# Buck.net
KiCad netlist of a schematic drawn in Altium Designer
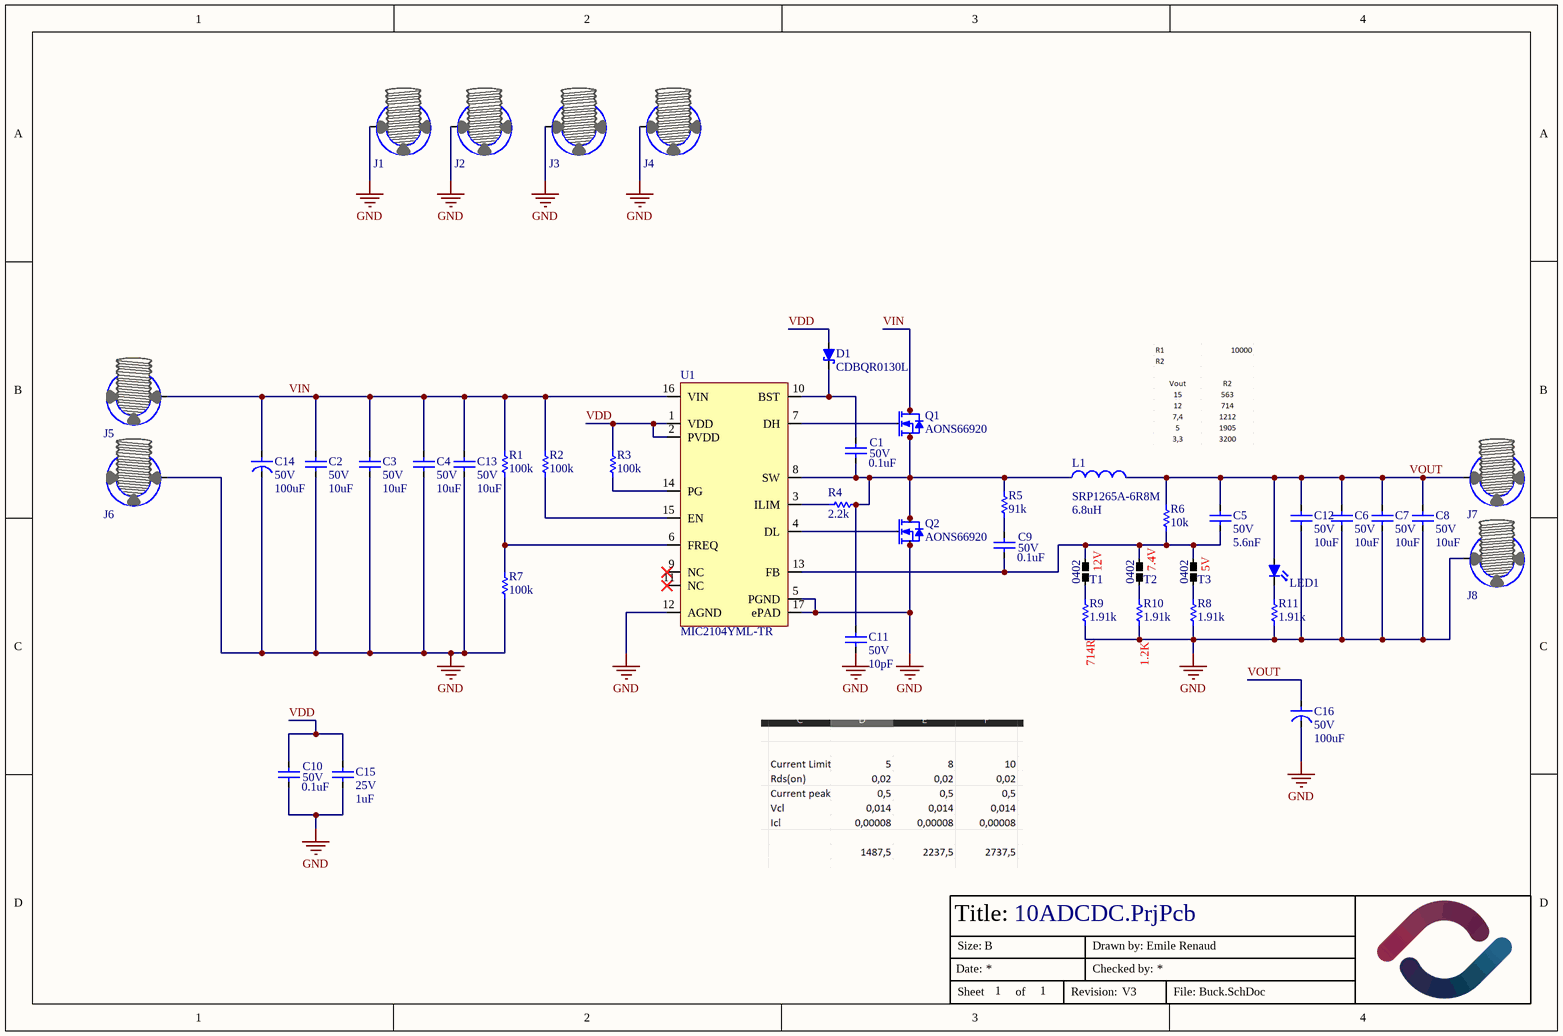
[diagram p0: Buck.SchDoc]

(export (version "E")
  (design (tool "Eeschema 10.0.6"))
  (components
    (comp (ref "C1")
      (value "0.1uF")
      (footprint "CAPACITOR-0603")
      (description "Capacitor-0603-0.1uF-50V-X7R")
      (fields (field (name "VOLT") "50V"))
      (libsource (lib "Capacitors") (part "Capacitor-0603-0.1uF-50V-X7R"))
    )
    (comp (ref "C2")
      (value "10uF")
      (footprint "CAPACITOR-1206")
      (description "Capacitor-1206-10uF-50V-X5R")
      (fields (field (name "VOLT") "50V"))
      (libsource (lib "Capacitors") (part "Capacitor-1206-10uF-50V-X5R"))
    )
    (comp (ref "C3")
      (value "10uF")
      (footprint "CAPACITOR-1206")
      (description "Capacitor-1206-10uF-50V-X5R")
      (fields (field (name "VOLT") "50V"))
      (libsource (lib "Capacitors") (part "Capacitor-1206-10uF-50V-X5R"))
    )
    (comp (ref "C4")
      (value "10uF")
      (footprint "CAPACITOR-1206")
      (description "Capacitor-1206-10uF-50V-X5R")
      (fields (field (name "VOLT") "50V"))
      (libsource (lib "Capacitors") (part "Capacitor-1206-10uF-50V-X5R"))
    )
    (comp (ref "C5")
      (value "5.6nF")
      (footprint "CAPACITOR-0603")
      (description "Capacitor-0603-5.6nF-50V-X7R")
      (fields (field (name "VOLT") "50V") (field (name "Comment") "Capacitor-0603-0.1uF-50V-X7R"))
      (libsource (lib "Capacitors") (part "Capacitor-0603-5.6nF-50V-X7R"))
    )
    (comp (ref "C6")
      (value "10uF")
      (footprint "CAPACITOR-1206")
      (description "Capacitor-1206-10uF-50V-X5R")
      (fields (field (name "VOLT") "50V"))
      (libsource (lib "Capacitors") (part "Capacitor-1206-10uF-50V-X5R"))
    )
    (comp (ref "C7")
      (value "10uF")
      (footprint "CAPACITOR-1206")
      (description "Capacitor-1206-10uF-50V-X5R")
      (fields (field (name "VOLT") "50V"))
      (libsource (lib "Capacitors") (part "Capacitor-1206-10uF-50V-X5R"))
    )
    (comp (ref "C8")
      (value "10uF")
      (footprint "CAPACITOR-1206")
      (description "Capacitor-1206-10uF-50V-X5R")
      (fields (field (name "VOLT") "50V"))
      (libsource (lib "Capacitors") (part "Capacitor-1206-10uF-50V-X5R"))
    )
    (comp (ref "C9")
      (value "0.1uF")
      (footprint "CAPACITOR-0603")
      (description "Capacitor-0603-0.1uF-50V-X7R")
      (fields (field (name "VOLT") "50V"))
      (libsource (lib "Capacitors") (part "Capacitor-0603-0.1uF-50V-X7R"))
    )
    (comp (ref "C10")
      (value "0.1uF")
      (footprint "CAPACITOR-0603")
      (description "Capacitor-0603-0.1uF-50V-X7R")
      (fields (field (name "VOLT") "50V"))
      (libsource (lib "Capacitors") (part "Capacitor-0603-0.1uF-50V-X7R"))
    )
    (comp (ref "C11")
      (value "10pF")
      (footprint "CAPACITOR-0603")
      (description "10 pF ±5% 50V Ceramic Capacitor C0G 0603 (1608 Metric)")
      (fields (field (name "VOLT") "50V") (field (name "Comment") "Capacitor-0603-10pF-50V-C0G"))
      (libsource (lib "Capacitors") (part "Capacitor-0603-10pF-50V-C0G"))
    )
    (comp (ref "C12")
      (value "10uF")
      (footprint "CAPACITOR-1206")
      (description "Capacitor-1206-10uF-50V-X5R")
      (fields (field (name "VOLT") "50V"))
      (libsource (lib "Capacitors") (part "Capacitor-1206-10uF-50V-X5R"))
    )
    (comp (ref "C13")
      (value "10uF")
      (footprint "CAPACITOR-1206")
      (description "Capacitor-1206-10uF-50V-X5R")
      (fields (field (name "VOLT") "50V"))
      (libsource (lib "Capacitors") (part "Capacitor-1206-10uF-50V-X5R"))
    )
    (comp (ref "C14")
      (value "100uF")
      (footprint "CAP_J-V_8X10P5_RUB")
      (description "CAP ALUM 100UF 20% 50V SMD")
      (fields (field (name "VOLT") "50V") (field (name "Comment") "CAP ALUM 100UF 20% 25V SMD"))
      (libsource (lib "Capacitors-Electrolytic") (part "Capacitor-100uF-50V-SMD"))
    )
    (comp (ref "C15")
      (value "1uF")
      (footprint "CAPACITOR-0603")
      (description "Capacitor-0603-1uF-25V-X5R")
      (fields (field (name "VOLT") "25V"))
      (libsource (lib "Capacitors") (part "Capacitor-0603-1uF-25V-X5R"))
    )
    (comp (ref "C16")
      (value "100uF")
      (footprint "CAP_J-V_8X10P5_RUB")
      (description "CAP ALUM 100UF 20% 50V SMD")
      (fields (field (name "VOLT") "50V") (field (name "Comment") "CAP ALUM 100UF 20% 25V SMD"))
      (libsource (lib "Capacitors-Electrolytic") (part "Capacitor-100uF-50V-SMD"))
    )
    (comp (ref "D1")
      (value "CDBQR0130L")
      (footprint "Diode-0402")
      (description "Diode SCHOTTKY  30 V 100mA Surface Mount 0402/SOD-923F")
      (libsource (lib "diodes") (part "CDBQR0130L"))
    )
    (comp (ref "J1")
      (value "hole")
      (footprint "HOLE-M2-Bolt")
      (description "Hole for M2 Bolt with 4mm pad")
      (libsource (lib "JumpersAndHoles") (part "Hole 2.3mm M2"))
    )
    (comp (ref "J2")
      (value "hole")
      (footprint "HOLE-M2-Bolt")
      (description "Hole for M2 Bolt with 4mm pad")
      (libsource (lib "JumpersAndHoles") (part "Hole 2.3mm M2"))
    )
    (comp (ref "J3")
      (value "hole")
      (footprint "HOLE-M2-Bolt")
      (description "Hole for M2 Bolt with 4mm pad")
      (libsource (lib "JumpersAndHoles") (part "Hole 2.3mm M2"))
    )
    (comp (ref "J4")
      (value "hole")
      (footprint "HOLE-M2-Bolt")
      (description "Hole for M2 Bolt with 4mm pad")
      (libsource (lib "JumpersAndHoles") (part "Hole 2.3mm M2"))
    )
    (comp (ref "J5")
      (value "hole")
      (footprint "HOLE-M2-Bolt")
      (description "Hole for M2 Bolt with 4mm pad")
      (libsource (lib "") (part "Hole 2.3mm M2_1"))
    )
    (comp (ref "J6")
      (value "hole")
      (footprint "HOLE-M2-Bolt")
      (description "Hole for M2 Bolt with 4mm pad")
      (libsource (lib "") (part "Hole 2.3mm M2_1"))
    )
    (comp (ref "J7")
      (value "hole")
      (footprint "HOLE-M2-Bolt")
      (description "Hole for M2 Bolt with 4mm pad")
      (libsource (lib "JumpersAndHoles") (part "Hole 2.3mm M2"))
    )
    (comp (ref "J8")
      (value "hole")
      (footprint "HOLE-M2-Bolt")
      (description "Hole for M2 Bolt with 4mm pad")
      (libsource (lib "JumpersAndHoles") (part "Hole 2.3mm M2"))
    )
    (comp (ref "L1")
      (value "SRP1265A-6R8M")
      (footprint "IND_SRP1265A-6R8M")
      (description "6.8 µH Shielded Drum Core, Wirewound Inductor 11.5 A 11.5mOhm Max Nonstandard")
      (fields (field (name "ALTIUM_VALUE") "6.8uH"))
      (libsource (lib "Inductors") (part "SRP1265A-6R8M"))
    )
    (comp (ref "LED1")
      (value "3147-B1931NB--20C007614U1930CT-ND")
      (footprint "LED-0603-2PIN")
      (description "LED BLUE CLEAR 0603 SMD")
      (libsource (lib "LEDs") (part "LED_BLUE"))
    )
    (comp (ref "Q1")
      (value "AONS66920")
      (footprint "DFN-8-5x6-Power")
      (description "N-Channel 100 V 17.5A (Ta), 48A (Tc) 5W (Ta), 56.5W (Tc) Surface Mount 8-DFN (5x6)")
      (libsource (lib "FET-N-Small") (part "AONS66920"))
    )
    (comp (ref "Q2")
      (value "AONS66920")
      (footprint "DFN-8-5x6-Power")
      (description "N-Channel 100 V 17.5A (Ta), 48A (Tc) 5W (Ta), 56.5W (Tc) Surface Mount 8-DFN (5x6)")
      (libsource (lib "FET-N-Small") (part "AONS66920"))
    )
    (comp (ref "R1")
      (value "100k")
      (footprint "Resistor-0603")
      (description "Resistor0603-100k")
      (fields (field (name "Comment") "SMT resistor"))
      (libsource (lib "Resistors") (part "Resistor-0603-100k"))
    )
    (comp (ref "R2")
      (value "100k")
      (footprint "Resistor-0603")
      (description "Resistor0603-100k")
      (fields (field (name "Comment") "SMT resistor"))
      (libsource (lib "Resistors") (part "Resistor-0603-100k"))
    )
    (comp (ref "R3")
      (value "100k")
      (footprint "Resistor-0603")
      (description "Resistor0603-100k")
      (fields (field (name "Comment") "SMT resistor"))
      (libsource (lib "Resistors") (part "Resistor-0603-100k"))
    )
    (comp (ref "R4")
      (value "2.2k")
      (footprint "Resistor-0603")
      (description "Resistor0603-2.2k")
      (fields (field (name "Comment") "SMT resistor"))
      (libsource (lib "Resistors") (part "Resistor-0603-2.2k"))
    )
    (comp (ref "R5")
      (value "91k")
      (footprint "Resistor-0603")
      (description "Resistor0603-91k")
      (fields (field (name "Comment") "SMT resistor"))
      (libsource (lib "Resistors") (part "Resistor-0603-91k"))
    )
    (comp (ref "R6")
      (value "10k")
      (footprint "Resistor-0603")
      (description "Resistor0603-10k")
      (fields (field (name "Comment") "SMT resistor"))
      (libsource (lib "Resistors") (part "Resistor-0603-10k"))
    )
    (comp (ref "R7")
      (value "100k")
      (footprint "Resistor-0603")
      (description "Resistor0603-100k")
      (fields (field (name "Comment") "SMT resistor"))
      (libsource (lib "Resistors") (part "Resistor-0603-100k"))
    )
    (comp (ref "R8")
      (value "1.91k")
      (footprint "Resistor-0603")
      (description "Resistor0603-1.91k")
      (fields (field (name "Comment") "SMT resistor"))
      (libsource (lib "Resistors") (part "Resistor-0603-1.91k"))
    )
    (comp (ref "R9")
      (value "1.91k")
      (footprint "Resistor-0603")
      (description "Resistor0603-1.91k")
      (fields (field (name "Comment") "SMT resistor"))
      (libsource (lib "Resistors") (part "Resistor-0603-1.91k"))
    )
    (comp (ref "R10")
      (value "1.91k")
      (footprint "Resistor-0603")
      (description "Resistor0603-1.91k")
      (fields (field (name "Comment") "SMT resistor"))
      (libsource (lib "Resistors") (part "Resistor-0603-1.91k"))
    )
    (comp (ref "R11")
      (value "1.91k")
      (footprint "Resistor-0603")
      (description "Resistor0603-1.91k")
      (fields (field (name "Comment") "SMT resistor"))
      (libsource (lib "Resistors") (part "Resistor-0603-1.91k"))
    )
    (comp (ref "T1")
      (value "NetTie_0402")
      (footprint "NetTie-0402")
      (libsource (lib "JumpersAndHoles") (part "NetTie_0402"))
    )
    (comp (ref "T2")
      (value "NetTie_0402")
      (footprint "NetTie-0402")
      (libsource (lib "JumpersAndHoles") (part "NetTie_0402"))
    )
    (comp (ref "T3")
      (value "NetTie_0402")
      (footprint "NetTie-0402")
      (libsource (lib "JumpersAndHoles") (part "NetTie_0402"))
    )
    (comp (ref "U1")
      (value "MIC2104YML-TR")
      (footprint "VQFN-16 3x3")
      (description "Buck Regulator Positive Output Step-Down DC-DC Controller IC 16-MLF® (3x3)")
      (libsource (lib "PMIC-VoltageRegulators-DCDCSwitchingRegulators") (part "MIC2104YML-TR"))
    )
  )
  (nets
    (net (code "1") (name "/VDD") (class "Default")
      (node (ref "C10") (pin "2") (pinfunction "2_2") (pintype "passive"))
      (node (ref "C15") (pin "2") (pinfunction "2_2") (pintype "passive"))
      (node (ref "D1") (pin "1") (pinfunction "A_1") (pintype "passive"))
      (node (ref "R3") (pin "2") (pinfunction "2_2") (pintype "passive"))
      (node (ref "U1") (pin "1") (pinfunction "VDD_1") (pintype "passive"))
      (node (ref "U1") (pin "2") (pinfunction "PVDD_2") (pintype "passive"))
    )
    (net (code "2") (name "/VIN") (class "Default")
      (node (ref "C13") (pin "2") (pinfunction "2_2") (pintype "passive"))
      (node (ref "C14") (pin "1") (pinfunction "1_1") (pintype "passive"))
      (node (ref "C2") (pin "2") (pinfunction "2_2") (pintype "passive"))
      (node (ref "C3") (pin "2") (pinfunction "2_2") (pintype "passive"))
      (node (ref "C4") (pin "2") (pinfunction "2_2") (pintype "passive"))
      (node (ref "J5") (pin "1") (pinfunction "1_1") (pintype "passive"))
      (node (ref "Q1") (pin "5") (pinfunction "D_5") (pintype "passive"))
      (node (ref "Q1") (pin "6") (pinfunction "D_6") (pintype "passive"))
      (node (ref "Q1") (pin "7") (pinfunction "D_7") (pintype "passive"))
      (node (ref "Q1") (pin "8") (pinfunction "D_8") (pintype "passive"))
      (node (ref "R1") (pin "2") (pinfunction "2_2") (pintype "passive"))
      (node (ref "R2") (pin "2") (pinfunction "2_2") (pintype "passive"))
      (node (ref "U1") (pin "16") (pinfunction "VIN_16") (pintype "passive"))
    )
    (net (code "3") (name "/VOUT") (class "Default")
      (node (ref "C12") (pin "2") (pinfunction "2_2") (pintype "passive"))
      (node (ref "C16") (pin "1") (pinfunction "1_1") (pintype "passive"))
      (node (ref "C5") (pin "2") (pinfunction "2_2") (pintype "passive"))
      (node (ref "C6") (pin "2") (pinfunction "2_2") (pintype "passive"))
      (node (ref "C7") (pin "2") (pinfunction "2_2") (pintype "passive"))
      (node (ref "C8") (pin "2") (pinfunction "2_2") (pintype "passive"))
      (node (ref "J7") (pin "1") (pinfunction "1_1") (pintype "passive"))
      (node (ref "L1") (pin "2") (pinfunction "2_2") (pintype "passive"))
      (node (ref "LED1") (pin "2") (pinfunction "R_2") (pintype "passive"))
      (node (ref "R6") (pin "2") (pinfunction "2_2") (pintype "passive"))
    )
    (net (code "4") (name "GND") (class "Default")
      (node (ref "C10") (pin "1") (pinfunction "1_1") (pintype "passive"))
      (node (ref "C11") (pin "1") (pinfunction "1_1") (pintype "passive"))
      (node (ref "C12") (pin "1") (pinfunction "1_1") (pintype "passive"))
      (node (ref "C13") (pin "1") (pinfunction "1_1") (pintype "passive"))
      (node (ref "C14") (pin "2") (pinfunction "2_2") (pintype "passive"))
      (node (ref "C15") (pin "1") (pinfunction "1_1") (pintype "passive"))
      (node (ref "C16") (pin "2") (pinfunction "2_2") (pintype "passive"))
      (node (ref "C2") (pin "1") (pinfunction "1_1") (pintype "passive"))
      (node (ref "C3") (pin "1") (pinfunction "1_1") (pintype "passive"))
      (node (ref "C4") (pin "1") (pinfunction "1_1") (pintype "passive"))
      (node (ref "C6") (pin "1") (pinfunction "1_1") (pintype "passive"))
      (node (ref "C7") (pin "1") (pinfunction "1_1") (pintype "passive"))
      (node (ref "C8") (pin "1") (pinfunction "1_1") (pintype "passive"))
      (node (ref "J1") (pin "1") (pinfunction "1_1") (pintype "passive"))
      (node (ref "J2") (pin "1") (pinfunction "1_1") (pintype "passive"))
      (node (ref "J3") (pin "1") (pinfunction "1_1") (pintype "passive"))
      (node (ref "J4") (pin "1") (pinfunction "1_1") (pintype "passive"))
      (node (ref "J6") (pin "1") (pinfunction "1_1") (pintype "passive"))
      (node (ref "J8") (pin "1") (pinfunction "1_1") (pintype "passive"))
      (node (ref "Q2") (pin "1") (pinfunction "S_1") (pintype "passive"))
      (node (ref "Q2") (pin "2") (pinfunction "S_2") (pintype "passive"))
      (node (ref "Q2") (pin "3") (pinfunction "S_3") (pintype "passive"))
      (node (ref "R10") (pin "1") (pinfunction "1_1") (pintype "passive"))
      (node (ref "R11") (pin "1") (pinfunction "1_1") (pintype "passive"))
      (node (ref "R7") (pin "1") (pinfunction "1_1") (pintype "passive"))
      (node (ref "R8") (pin "1") (pinfunction "1_1") (pintype "passive"))
      (node (ref "R9") (pin "1") (pinfunction "1_1") (pintype "passive"))
      (node (ref "U1") (pin "12") (pinfunction "AGND_12") (pintype "passive"))
      (node (ref "U1") (pin "17") (pinfunction "ePAD_17") (pintype "passive"))
      (node (ref "U1") (pin "5") (pinfunction "PGND_5") (pintype "passive"))
    )
    (net (code "5") (name "Net-(C9-Pad2)") (class "Default")
      (node (ref "C9") (pin "2") (pinfunction "2_2") (pintype "passive"))
      (node (ref "R5") (pin "1") (pinfunction "1_1") (pintype "passive"))
    )
    (net (code "6") (name "Net-(D1-K)") (class "Default")
      (node (ref "C1") (pin "2") (pinfunction "2_2") (pintype "passive"))
      (node (ref "D1") (pin "2") (pinfunction "K_2") (pintype "passive"))
      (node (ref "U1") (pin "10") (pinfunction "BST_10") (pintype "passive"))
    )
    (net (code "7") (name "Net-(LED1-K)") (class "Default")
      (node (ref "LED1") (pin "1") (pinfunction "K_1") (pintype "passive"))
      (node (ref "R11") (pin "2") (pinfunction "2_2") (pintype "passive"))
    )
    (net (code "8") (name "Net-(Q1-G)") (class "Default")
      (node (ref "Q1") (pin "4") (pinfunction "G_4") (pintype "passive"))
      (node (ref "U1") (pin "7") (pinfunction "DH_7") (pintype "passive"))
    )
    (net (code "9") (name "Net-(Q2-G)") (class "Default")
      (node (ref "Q2") (pin "4") (pinfunction "G_4") (pintype "passive"))
      (node (ref "U1") (pin "4") (pinfunction "DL_4") (pintype "passive"))
    )
    (net (code "10") (name "Net-(R8-Pad2)") (class "Default")
      (node (ref "R8") (pin "2") (pinfunction "2_2") (pintype "passive"))
      (node (ref "T3") (pin "2") (pinfunction "2_2") (pintype "passive"))
    )
    (net (code "11") (name "Net-(R9-Pad2)") (class "Default")
      (node (ref "R9") (pin "2") (pinfunction "2_2") (pintype "passive"))
      (node (ref "T1") (pin "2") (pinfunction "2_2") (pintype "passive"))
    )
    (net (code "12") (name "Net-(R10-Pad2)") (class "Default")
      (node (ref "R10") (pin "2") (pinfunction "2_2") (pintype "passive"))
      (node (ref "T2") (pin "2") (pinfunction "2_2") (pintype "passive"))
    )
    (net (code "13") (name "Net-(U1-EN)") (class "Default")
      (node (ref "R2") (pin "1") (pinfunction "1_1") (pintype "passive"))
      (node (ref "U1") (pin "15") (pinfunction "EN_15") (pintype "passive"))
    )
    (net (code "14") (name "Net-(U1-FB)") (class "Default")
      (node (ref "C5") (pin "1") (pinfunction "1_1") (pintype "passive"))
      (node (ref "C9") (pin "1") (pinfunction "1_1") (pintype "passive"))
      (node (ref "R6") (pin "1") (pinfunction "1_1") (pintype "passive"))
      (node (ref "T1") (pin "1") (pinfunction "1_1") (pintype "passive"))
      (node (ref "T2") (pin "1") (pinfunction "1_1") (pintype "passive"))
      (node (ref "T3") (pin "1") (pinfunction "1_1") (pintype "passive"))
      (node (ref "U1") (pin "13") (pinfunction "FB_13") (pintype "passive"))
    )
    (net (code "15") (name "Net-(U1-FREQ)") (class "Default")
      (node (ref "R1") (pin "1") (pinfunction "1_1") (pintype "passive"))
      (node (ref "R7") (pin "2") (pinfunction "2_2") (pintype "passive"))
      (node (ref "U1") (pin "6") (pinfunction "FREQ_6") (pintype "passive"))
    )
    (net (code "16") (name "Net-(U1-ILIM)") (class "Default")
      (node (ref "R4") (pin "1") (pinfunction "1_1") (pintype "passive"))
      (node (ref "U1") (pin "3") (pinfunction "ILIM_3") (pintype "passive"))
    )
    (net (code "17") (name "Net-(U1-PG)") (class "Default")
      (node (ref "R3") (pin "1") (pinfunction "1_1") (pintype "passive"))
      (node (ref "U1") (pin "14") (pinfunction "PG_14") (pintype "passive"))
    )
    (net (code "18") (name "Net-(U1-SW)") (class "Default")
      (node (ref "C1") (pin "1") (pinfunction "1_1") (pintype "passive"))
      (node (ref "C11") (pin "2") (pinfunction "2_2") (pintype "passive"))
      (node (ref "L1") (pin "1") (pinfunction "1_1") (pintype "passive"))
      (node (ref "Q1") (pin "1") (pinfunction "S_1") (pintype "passive"))
      (node (ref "Q1") (pin "2") (pinfunction "S_2") (pintype "passive"))
      (node (ref "Q1") (pin "3") (pinfunction "S_3") (pintype "passive"))
      (node (ref "Q2") (pin "5") (pinfunction "D_5") (pintype "passive"))
      (node (ref "Q2") (pin "6") (pinfunction "D_6") (pintype "passive"))
      (node (ref "Q2") (pin "7") (pinfunction "D_7") (pintype "passive"))
      (node (ref "Q2") (pin "8") (pinfunction "D_8") (pintype "passive"))
      (node (ref "R4") (pin "2") (pinfunction "2_2") (pintype "passive"))
      (node (ref "R5") (pin "2") (pinfunction "2_2") (pintype "passive"))
      (node (ref "U1") (pin "8") (pinfunction "SW_8") (pintype "passive"))
    )
    (net (code "19") (name "unconnected-(U1-NC-Pad9)") (class "Default")
      (node (ref "U1") (pin "9") (pinfunction "NC_9") (pintype "passive+no_connect"))
    )
    (net (code "20") (name "unconnected-(U1-NC-Pad11)") (class "Default")
      (node (ref "U1") (pin "11") (pinfunction "NC_11") (pintype "passive+no_connect"))
    )
  )
)
